# audio_amplifier.net
KiCad netlist of a schematic drawn in EAGLE
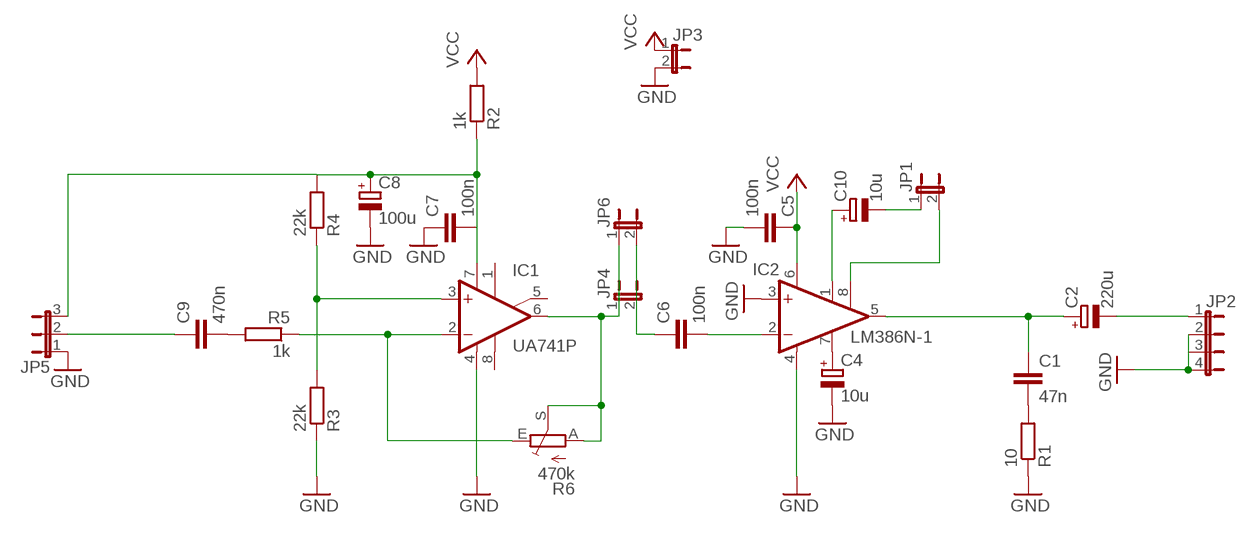
[diagram p0: schematic, sheet 1]

(export (version "E")
  (design (tool "Eeschema 10.0.6"))
  (components
    (comp (ref "C1")
      (value "47n")
      (footprint "eagle-import:C025-024X044")
      (libsource (lib "eagle-import") (part "C-EU025-024X044"))
    )
    (comp (ref "C2")
      (value "220u")
      (footprint "eagle-import:E2,5-6")
      (libsource (lib "eagle-import") (part "CPOL-EUE2.5-6"))
    )
    (comp (ref "C4")
      (value "10u")
      (footprint "eagle-import:B_3528-21R")
      (libsource (lib "eagle-import") (part "CPOL-EUB/3528-21R"))
    )
    (comp (ref "C5")
      (value "100n")
      (footprint "eagle-import:C050-025X075")
      (libsource (lib "eagle-import") (part "C-EU050-025X075"))
    )
    (comp (ref "C6")
      (value "100n")
      (footprint "eagle-import:C050-025X075")
      (libsource (lib "eagle-import") (part "C-EU050-025X075"))
    )
    (comp (ref "C7")
      (value "100n")
      (footprint "eagle-import:C025-024X044")
      (libsource (lib "eagle-import") (part "C-EU025-024X044"))
    )
    (comp (ref "C8")
      (value "100u")
      (footprint "eagle-import:E2,5-5")
      (libsource (lib "eagle-import") (part "CPOL-EUE2.5-5"))
    )
    (comp (ref "C9")
      (value "470n")
      (footprint "eagle-import:C050-025X075")
      (libsource (lib "eagle-import") (part "C-EU050-025X075"))
    )
    (comp (ref "C10")
      (value "10u")
      (footprint "eagle-import:E2,5-5")
      (libsource (lib "eagle-import") (part "CPOL-EUE2.5-5"))
    )
    (comp (ref "IC1")
      (value "UA741P")
      (footprint "eagle-import:DIL08")
      (libsource (lib "eagle-import") (part "741PUA"))
    )
    (comp (ref "IC2")
      (value "LM386N-1")
      (footprint "eagle-import:DIL08")
      (libsource (lib "eagle-import") (part "LM386?-N1"))
    )
    (comp (ref "JP1")
      (value "JP1E")
      (footprint "eagle-import:JP1")
      (libsource (lib "eagle-import") (part "JP1E"))
    )
    (comp (ref "JP2")
      (value "JP4E")
      (footprint "eagle-import:JP4")
      (libsource (lib "eagle-import") (part "JP4E"))
    )
    (comp (ref "JP3")
      (value "JP1E")
      (footprint "eagle-import:JP1")
      (libsource (lib "eagle-import") (part "JP1E"))
    )
    (comp (ref "JP4")
      (value "JP1E")
      (footprint "eagle-import:JP1")
      (libsource (lib "eagle-import") (part "JP1E"))
    )
    (comp (ref "JP5")
      (value "JP2E")
      (footprint "eagle-import:JP2")
      (libsource (lib "eagle-import") (part "JP2E"))
    )
    (comp (ref "JP6")
      (value "JP1E")
      (footprint "eagle-import:JP1")
      (libsource (lib "eagle-import") (part "JP1E"))
    )
    (comp (ref "R1")
      (value "10")
      (footprint "eagle-import:0204_5")
      (libsource (lib "eagle-import") (part "R-EU_0204/5"))
    )
    (comp (ref "R2")
      (value "1k")
      (footprint "eagle-import:0204_5")
      (libsource (lib "eagle-import") (part "R-EU_0204/5"))
    )
    (comp (ref "R3")
      (value "22k")
      (footprint "eagle-import:0204_7")
      (libsource (lib "eagle-import") (part "R-EU_0204/7"))
    )
    (comp (ref "R4")
      (value "22k")
      (footprint "eagle-import:0204_5")
      (libsource (lib "eagle-import") (part "R-EU_0204/5"))
    )
    (comp (ref "R5")
      (value "1k")
      (footprint "eagle-import:0204V")
      (libsource (lib "eagle-import") (part "R-EU_0204/2V"))
    )
    (comp (ref "R6")
      (value "470k")
      (footprint "eagle-import:B64Y")
      (libsource (lib "eagle-import") (part "TRIM_EU-B64Y"))
    )
  )
  (nets
    (net (code "1") (name "GND") (class "Default")
      (node (ref "C4") (pin "-") (pinfunction "-_-") (pintype "passive"))
      (node (ref "C5") (pin "2") (pinfunction "2_2") (pintype "passive"))
      (node (ref "C7") (pin "1") (pinfunction "1_1") (pintype "passive"))
      (node (ref "C8") (pin "-") (pinfunction "-_-") (pintype "passive"))
      (node (ref "IC1") (pin "4") (pinfunction "V-_4") (pintype "power_in"))
      (node (ref "IC2") (pin "3") (pinfunction "+IN_3") (pintype "input"))
      (node (ref "IC2") (pin "4") (pinfunction "GND_4") (pintype "power_in"))
      (node (ref "JP2") (pin "2") (pinfunction "2_2") (pintype "passive"))
      (node (ref "JP2") (pin "3") (pinfunction "3_3") (pintype "passive"))
      (node (ref "JP2") (pin "4") (pinfunction "4_4") (pintype "passive"))
      (node (ref "JP3") (pin "2") (pinfunction "2_2") (pintype "passive"))
      (node (ref "JP5") (pin "1") (pinfunction "1_1") (pintype "passive"))
      (node (ref "R1") (pin "1") (pinfunction "1_1") (pintype "passive"))
      (node (ref "R3") (pin "1") (pinfunction "1_1") (pintype "passive"))
    )
    (net (code "2") (name "Net-(C1-Pad2)") (class "Default")
      (node (ref "C1") (pin "2") (pinfunction "2_2") (pintype "passive"))
      (node (ref "R1") (pin "2") (pinfunction "2_2") (pintype "passive"))
    )
    (net (code "3") (name "Net-(C2-Pad-)") (class "Default")
      (node (ref "C2") (pin "-") (pinfunction "-_-") (pintype "passive"))
      (node (ref "JP2") (pin "1") (pinfunction "1_1") (pintype "passive"))
    )
    (net (code "4") (name "Net-(C6-Pad1)") (class "Default")
      (node (ref "C6") (pin "1") (pinfunction "1_1") (pintype "passive"))
      (node (ref "JP4") (pin "2") (pinfunction "2_2") (pintype "passive"))
      (node (ref "JP6") (pin "2") (pinfunction "2_2") (pintype "passive"))
    )
    (net (code "5") (name "Net-(C9-Pad1)") (class "Default")
      (node (ref "C9") (pin "1") (pinfunction "1_1") (pintype "passive"))
      (node (ref "JP5") (pin "2") (pinfunction "2_2") (pintype "passive"))
    )
    (net (code "6") (name "Net-(C9-Pad2)") (class "Default")
      (node (ref "C9") (pin "2") (pinfunction "2_2") (pintype "passive"))
      (node (ref "R5") (pin "2") (pinfunction "2_2") (pintype "passive"))
    )
    (net (code "7") (name "Net-(C10-Pad+)") (class "Default")
      (node (ref "C10") (pin "+") (pinfunction "+_+") (pintype "passive"))
      (node (ref "IC2") (pin "1") (pinfunction "GAIN_1") (pintype "passive"))
    )
    (net (code "8") (name "Net-(C10-Pad-)") (class "Default")
      (node (ref "C10") (pin "-") (pinfunction "-_-") (pintype "passive"))
      (node (ref "JP1") (pin "1") (pinfunction "1_1") (pintype "passive"))
    )
    (net (code "9") (name "Net-(IC1-+IN)") (class "Default")
      (node (ref "IC1") (pin "3") (pinfunction "+IN_3") (pintype "input"))
      (node (ref "R3") (pin "2") (pinfunction "2_2") (pintype "passive"))
      (node (ref "R4") (pin "1") (pinfunction "1_1") (pintype "passive"))
    )
    (net (code "10") (name "Net-(IC1--IN)") (class "Default")
      (node (ref "IC1") (pin "2") (pinfunction "-IN_2") (pintype "input"))
      (node (ref "R5") (pin "1") (pinfunction "1_1") (pintype "passive"))
      (node (ref "R6") (pin "E") (pinfunction "E_E") (pintype "passive"))
    )
    (net (code "11") (name "Net-(IC1-OUT)") (class "Default")
      (node (ref "IC1") (pin "6") (pinfunction "OUT_6") (pintype "output"))
      (node (ref "JP4") (pin "1") (pinfunction "1_1") (pintype "passive"))
      (node (ref "JP6") (pin "1") (pinfunction "1_1") (pintype "passive"))
      (node (ref "R6") (pin "A") (pinfunction "A_A") (pintype "passive"))
      (node (ref "R6") (pin "S") (pinfunction "S_S") (pintype "passive"))
    )
    (net (code "12") (name "Net-(IC1-V+)") (class "Default")
      (node (ref "C7") (pin "2") (pinfunction "2_2") (pintype "passive"))
      (node (ref "C8") (pin "+") (pinfunction "+_+") (pintype "passive"))
      (node (ref "IC1") (pin "7") (pinfunction "V+_7") (pintype "power_in"))
      (node (ref "JP5") (pin "3") (pinfunction "3_3") (pintype "passive"))
      (node (ref "R2") (pin "1") (pinfunction "1_1") (pintype "passive"))
      (node (ref "R4") (pin "2") (pinfunction "2_2") (pintype "passive"))
    )
    (net (code "13") (name "Net-(IC2--IN)") (class "Default")
      (node (ref "C6") (pin "2") (pinfunction "2_2") (pintype "passive"))
      (node (ref "IC2") (pin "2") (pinfunction "-IN_2") (pintype "input"))
    )
    (net (code "14") (name "Net-(IC2-BYPASS)") (class "Default")
      (node (ref "C4") (pin "+") (pinfunction "+_+") (pintype "passive"))
      (node (ref "IC2") (pin "7") (pinfunction "BYPASS_7") (pintype "passive"))
    )
    (net (code "15") (name "Net-(IC2-GAIN-Pad8)") (class "Default")
      (node (ref "IC2") (pin "8") (pinfunction "GAIN_8") (pintype "passive"))
      (node (ref "JP1") (pin "2") (pinfunction "2_2") (pintype "passive"))
    )
    (net (code "16") (name "Net-(IC2-OUT)") (class "Default")
      (node (ref "C1") (pin "1") (pinfunction "1_1") (pintype "passive"))
      (node (ref "C2") (pin "+") (pinfunction "+_+") (pintype "passive"))
      (node (ref "IC2") (pin "5") (pinfunction "OUT_5") (pintype "output"))
    )
    (net (code "17") (name "VCC") (class "Default")
      (node (ref "C5") (pin "1") (pinfunction "1_1") (pintype "passive"))
      (node (ref "IC2") (pin "6") (pinfunction "VS_6") (pintype "power_in"))
      (node (ref "JP3") (pin "1") (pinfunction "1_1") (pintype "passive"))
      (node (ref "R2") (pin "2") (pinfunction "2_2") (pintype "passive"))
    )
    (net (code "18") (name "unconnected-(IC1-ON1-Pad1)") (class "Default")
      (node (ref "IC1") (pin "1") (pinfunction "ON1_1") (pintype "passive"))
    )
    (net (code "19") (name "unconnected-(IC1-ON2-Pad5)") (class "Default")
      (node (ref "IC1") (pin "5") (pinfunction "ON2_5") (pintype "passive"))
    )
    (net (code "20") (name "unconnected-(IC1-OPT-Pad8)") (class "Default")
      (node (ref "IC1") (pin "8") (pinfunction "OPT_8") (pintype "passive"))
    )
  )
)
